# motorEncoder.net
KiCad netlist of a schematic drawn in Altium Designer
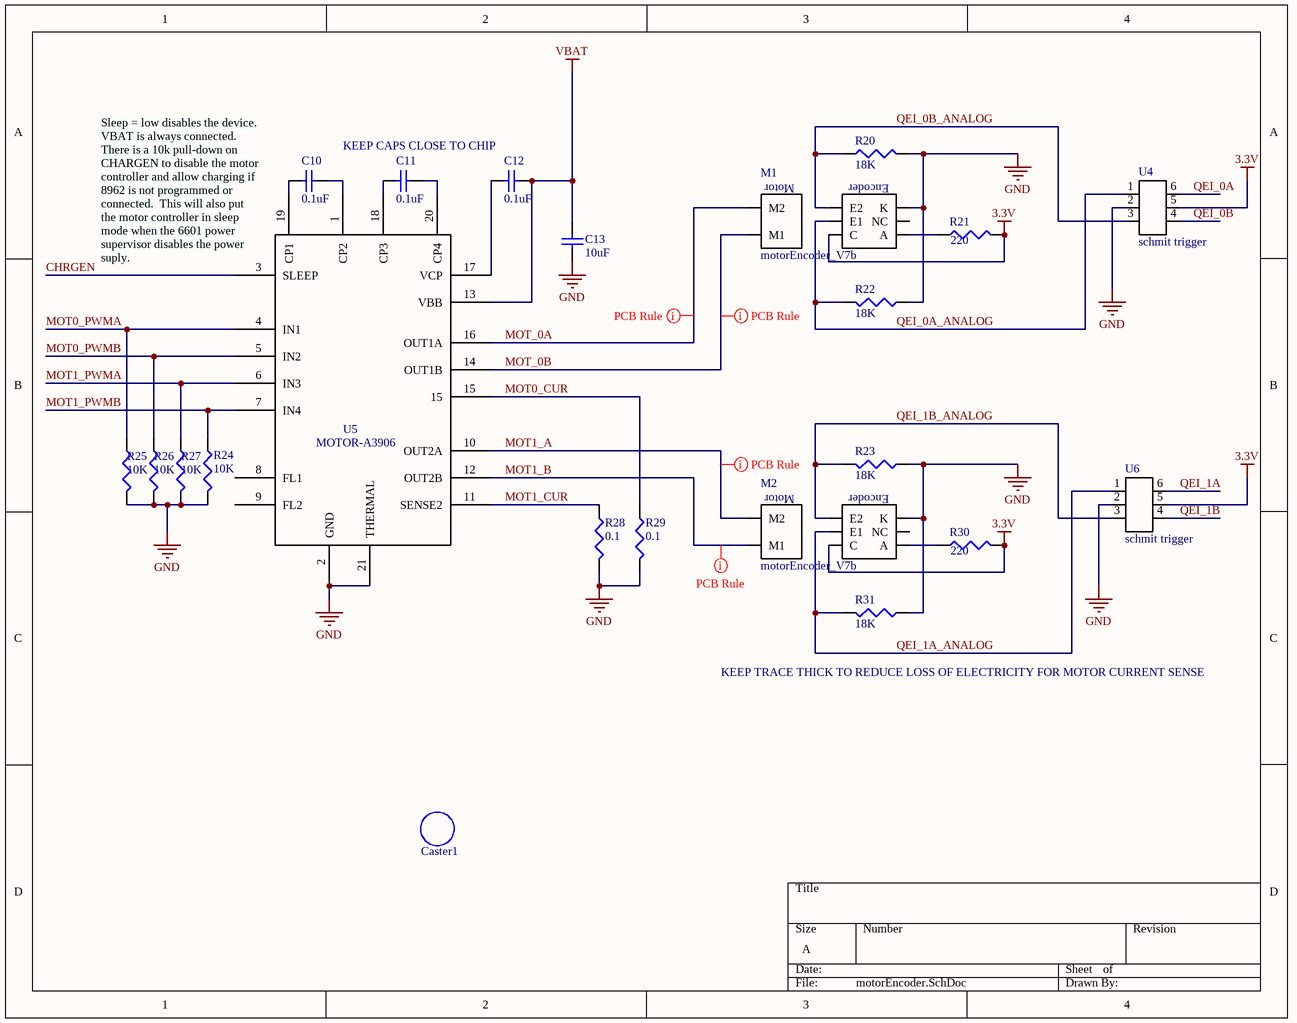
[diagram p0: motorEncoder.SchDoc]

(export (version "E")
  (design (tool "Eeschema 10.0.6"))
  (components
    (comp (ref "C10")
      (value "0.1uF")
      (footprint "CAPC1005L")
      (description "Capacitor (Semiconductor SIM Model)")
      (fields (field (name "Comment") "Cap Semi") (field (name "PUBLISHER") "Altium Limited"))
      (libsource (lib "Miscellaneous Devices") (part "Cap Semi"))
    )
    (comp (ref "C11")
      (value "0.1uF")
      (footprint "CAPC1005L")
      (description "Capacitor (Semiconductor SIM Model)")
      (fields (field (name "Comment") "Cap Semi") (field (name "PUBLISHER") "Altium Limited"))
      (libsource (lib "Miscellaneous Devices") (part "Cap Semi"))
    )
    (comp (ref "C12")
      (value "0.1uF")
      (footprint "CAPC1005L")
      (description "Capacitor (Semiconductor SIM Model)")
      (fields (field (name "Comment") "Cap Semi") (field (name "PUBLISHER") "Altium Limited"))
      (libsource (lib "Miscellaneous Devices") (part "Cap Semi"))
    )
    (comp (ref "C13")
      (value "10uF")
      (footprint "CAPC1608L")
      (description "Capacitor (Semiconductor SIM Model)")
      (fields (field (name "Comment") "Cap Semi") (field (name "PUBLISHER") "Altium Limited"))
      (libsource (lib "Miscellaneous Devices") (part "Cap Semi"))
    )
    (comp (ref "Caster1")
      (value "non connect")
      (footprint "3/4\"CASTER2")
      (description "This is just a space saver to get the caster onto the pcb")
      (libsource (lib "mrone") (part "Caster 3/4in"))
    )
    (comp (ref "M1")
      (value "motorEncoder_V7b")
      (footprint "motorEncoder_V7b")
      (libsource (lib "mrone") (part "motorEncoder_V7b"))
    )
    (comp (ref "M2")
      (value "motorEncoder_V7b")
      (footprint "motorEncoder_V7b")
      (libsource (lib "mrone") (part "motorEncoder_V7b"))
    )
    (comp (ref "R20")
      (value "18K")
      (footprint "RESC1608L")
      (description "Resistor")
      (fields (field (name "PUBLISHER") "Altium Limited"))
      (libsource (lib "Miscellaneous Devices") (part "Res3"))
    )
    (comp (ref "R21")
      (value "220")
      (footprint "RESC1608L")
      (description "Resistor")
      (fields (field (name "PUBLISHER") "Altium Limited"))
      (libsource (lib "Miscellaneous Devices") (part "Res3"))
    )
    (comp (ref "R22")
      (value "18K")
      (footprint "RESC1608L")
      (description "Resistor")
      (fields (field (name "PUBLISHER") "Altium Limited"))
      (libsource (lib "Miscellaneous Devices") (part "Res3"))
    )
    (comp (ref "R23")
      (value "18K")
      (footprint "RESC1608L")
      (description "Resistor")
      (fields (field (name "PUBLISHER") "Altium Limited"))
      (libsource (lib "Miscellaneous Devices") (part "Res3"))
    )
    (comp (ref "R24")
      (value "10K")
      (footprint "RESC1608L")
      (description "Resistor")
      (fields (field (name "Comment") "Res3") (field (name "PUBLISHER") "Altium Limited"))
      (libsource (lib "Miscellaneous Devices") (part "Res3"))
    )
    (comp (ref "R25")
      (value "10K")
      (footprint "RESC1608L")
      (description "Resistor")
      (fields (field (name "Comment") "Res3") (field (name "PUBLISHER") "Altium Limited"))
      (libsource (lib "Miscellaneous Devices") (part "Res3"))
    )
    (comp (ref "R26")
      (value "10K")
      (footprint "RESC1608L")
      (description "Resistor")
      (fields (field (name "Comment") "Res3") (field (name "PUBLISHER") "Altium Limited"))
      (libsource (lib "Miscellaneous Devices") (part "Res3"))
    )
    (comp (ref "R27")
      (value "10K")
      (footprint "RESC1608L")
      (description "Resistor")
      (fields (field (name "Comment") "Res3") (field (name "PUBLISHER") "Altium Limited"))
      (libsource (lib "Miscellaneous Devices") (part "Res3"))
    )
    (comp (ref "R28")
      (value "0.1")
      (footprint "RESC1608L")
      (description "Resistor")
      (fields (field (name "Comment") "Res3") (field (name "PUBLISHER") "Altium Limited"))
      (libsource (lib "Miscellaneous Devices") (part "Res3"))
    )
    (comp (ref "R29")
      (value "0.1")
      (footprint "RESC1608L")
      (description "Resistor")
      (fields (field (name "Comment") "Res3") (field (name "PUBLISHER") "Altium Limited"))
      (libsource (lib "Miscellaneous Devices") (part "Res3"))
    )
    (comp (ref "R30")
      (value "220")
      (footprint "RESC1608L")
      (description "Resistor")
      (fields (field (name "PUBLISHER") "Altium Limited"))
      (libsource (lib "Miscellaneous Devices") (part "Res3"))
    )
    (comp (ref "R31")
      (value "18K")
      (footprint "RESC1608L")
      (description "Resistor")
      (fields (field (name "PUBLISHER") "Altium Limited"))
      (libsource (lib "Miscellaneous Devices") (part "Res3"))
    )
    (comp (ref "U4")
      (value "schmit trigger")
      (footprint "DCK(R-PDSO-C6)")
      (libsource (lib "mrone") (part "schmit trigger"))
    )
    (comp (ref "U5")
      (value "MOTOR-A3906")
      (footprint "QFN-20")
      (libsource (lib "V2_altium") (part "MOTOR-A3906"))
    )
    (comp (ref "U6")
      (value "schmit trigger")
      (footprint "DCK(R-PDSO-C6)")
      (libsource (lib "mrone") (part "schmit trigger"))
    )
  )
  (nets
    (net (code "2") (name "/CHRGEN") (class "Default")
      (node (ref "U5") (pin "3") (pinfunction "SLEEP_3") (pintype "passive"))
    )
    (net (code "3") (name "/MOT0_CUR") (class "Default")
      (node (ref "R29") (pin "1") (pinfunction "1_1") (pintype "passive"))
      (node (ref "U5") (pin "15") (pinfunction "15_15") (pintype "passive"))
    )
    (net (code "4") (name "/MOT0_PWMA") (class "Default")
      (node (ref "R25") (pin "1") (pinfunction "1_1") (pintype "passive"))
      (node (ref "U5") (pin "4") (pinfunction "IN1_4") (pintype "passive"))
    )
    (net (code "5") (name "/MOT0_PWMB") (class "Default")
      (node (ref "R26") (pin "1") (pinfunction "1_1") (pintype "passive"))
      (node (ref "U5") (pin "5") (pinfunction "IN2_5") (pintype "passive"))
    )
    (net (code "6") (name "/MOT1_A") (class "Default")
      (node (ref "M2") (pin "M2") (pinfunction "M2_M2") (pintype "passive"))
      (node (ref "U5") (pin "10") (pinfunction "OUT2A_10") (pintype "passive"))
    )
    (net (code "7") (name "/MOT1_B") (class "Default")
      (node (ref "M2") (pin "M1") (pinfunction "M1_M1") (pintype "passive"))
      (node (ref "U5") (pin "12") (pinfunction "OUT2B_12") (pintype "passive"))
    )
    (net (code "8") (name "/MOT1_CUR") (class "Default")
      (node (ref "R28") (pin "1") (pinfunction "1_1") (pintype "passive"))
      (node (ref "U5") (pin "11") (pinfunction "SENSE2_11") (pintype "passive"))
    )
    (net (code "9") (name "/MOT1_PWMA") (class "Default")
      (node (ref "R27") (pin "1") (pinfunction "1_1") (pintype "passive"))
      (node (ref "U5") (pin "6") (pinfunction "IN3_6") (pintype "passive"))
    )
    (net (code "10") (name "/MOT1_PWMB") (class "Default")
      (node (ref "R24") (pin "1") (pinfunction "1_1") (pintype "passive"))
      (node (ref "U5") (pin "7") (pinfunction "IN4_7") (pintype "passive"))
    )
    (net (code "11") (name "/MOT_0A") (class "Default")
      (node (ref "M1") (pin "M2") (pinfunction "M2_M2") (pintype "passive"))
      (node (ref "U5") (pin "16") (pinfunction "OUT1A_16") (pintype "passive"))
    )
    (net (code "12") (name "/MOT_0B") (class "Default")
      (node (ref "M1") (pin "M1") (pinfunction "M1_M1") (pintype "passive"))
      (node (ref "U5") (pin "14") (pinfunction "OUT1B_14") (pintype "passive"))
    )
    (net (code "13") (name "/QEI_0A") (class "Default")
      (node (ref "U4") (pin "6") (pinfunction "4_6") (pintype "passive"))
    )
    (net (code "14") (name "/QEI_0A_ANALOG") (class "Default")
      (node (ref "M1") (pin "E1") (pinfunction "E1_E1") (pintype "passive"))
      (node (ref "R22") (pin "2") (pinfunction "2_2") (pintype "passive"))
      (node (ref "U4") (pin "1") (pinfunction "1_1") (pintype "passive"))
    )
    (net (code "15") (name "/QEI_0B") (class "Default")
      (node (ref "U4") (pin "4") (pinfunction "4_4") (pintype "passive"))
    )
    (net (code "16") (name "/QEI_0B_ANALOG") (class "Default")
      (node (ref "M1") (pin "E2") (pinfunction "E2_E2") (pintype "passive"))
      (node (ref "R20") (pin "1") (pinfunction "1_1") (pintype "passive"))
      (node (ref "U4") (pin "3") (pinfunction "3_3") (pintype "passive"))
    )
    (net (code "17") (name "/QEI_1A") (class "Default")
      (node (ref "U6") (pin "6") (pinfunction "4_6") (pintype "passive"))
    )
    (net (code "18") (name "/QEI_1A_ANALOG") (class "Default")
      (node (ref "M2") (pin "E1") (pinfunction "E1_E1") (pintype "passive"))
      (node (ref "R31") (pin "2") (pinfunction "2_2") (pintype "passive"))
      (node (ref "U6") (pin "1") (pinfunction "1_1") (pintype "passive"))
    )
    (net (code "19") (name "/QEI_1B") (class "Default")
      (node (ref "U6") (pin "4") (pinfunction "4_4") (pintype "passive"))
    )
    (net (code "20") (name "/QEI_1B_ANALOG") (class "Default")
      (node (ref "M2") (pin "E2") (pinfunction "E2_E2") (pintype "passive"))
      (node (ref "R23") (pin "2") (pinfunction "2_2") (pintype "passive"))
      (node (ref "U6") (pin "3") (pinfunction "3_3") (pintype "passive"))
    )
    (net (code "21") (name "3.3V") (class "Default")
      (node (ref "M1") (pin "C") (pinfunction "C_C") (pintype "passive"))
      (node (ref "M2") (pin "C") (pinfunction "C_C") (pintype "passive"))
      (node (ref "R21") (pin "2") (pinfunction "2_2") (pintype "passive"))
      (node (ref "R30") (pin "2") (pinfunction "2_2") (pintype "passive"))
      (node (ref "U4") (pin "5") (pinfunction "5_5") (pintype "passive"))
      (node (ref "U6") (pin "5") (pinfunction "5_5") (pintype "passive"))
    )
    (net (code "22") (name "GND") (class "Default")
      (node (ref "C13") (pin "1") (pinfunction "1_1") (pintype "passive"))
      (node (ref "M1") (pin "K") (pinfunction "K_K") (pintype "passive"))
      (node (ref "M2") (pin "K") (pinfunction "K_K") (pintype "passive"))
      (node (ref "R20") (pin "2") (pinfunction "2_2") (pintype "passive"))
      (node (ref "R22") (pin "1") (pinfunction "1_1") (pintype "passive"))
      (node (ref "R23") (pin "1") (pinfunction "1_1") (pintype "passive"))
      (node (ref "R24") (pin "2") (pinfunction "2_2") (pintype "passive"))
      (node (ref "R25") (pin "2") (pinfunction "2_2") (pintype "passive"))
      (node (ref "R26") (pin "2") (pinfunction "2_2") (pintype "passive"))
      (node (ref "R27") (pin "2") (pinfunction "2_2") (pintype "passive"))
      (node (ref "R28") (pin "2") (pinfunction "2_2") (pintype "passive"))
      (node (ref "R29") (pin "2") (pinfunction "2_2") (pintype "passive"))
      (node (ref "R31") (pin "1") (pinfunction "1_1") (pintype "passive"))
      (node (ref "U4") (pin "2") (pinfunction "2_2") (pintype "passive"))
      (node (ref "U5") (pin "2") (pinfunction "GND_2") (pintype "passive"))
      (node (ref "U5") (pin "21") (pinfunction "THERMAL_21") (pintype "passive"))
      (node (ref "U6") (pin "2") (pinfunction "2_2") (pintype "passive"))
    )
    (net (code "23") (name "Net-(M1-PadA)") (class "Default")
      (node (ref "M1") (pin "A") (pinfunction "A_A") (pintype "passive"))
      (node (ref "R21") (pin "1") (pinfunction "1_1") (pintype "passive"))
    )
    (net (code "24") (name "Net-(M2-PadA)") (class "Default")
      (node (ref "M2") (pin "A") (pinfunction "A_A") (pintype "passive"))
      (node (ref "R30") (pin "1") (pinfunction "1_1") (pintype "passive"))
    )
    (net (code "25") (name "Net-(U5-CP1)") (class "Default")
      (node (ref "C10") (pin "1") (pinfunction "1_1") (pintype "passive"))
      (node (ref "U5") (pin "19") (pinfunction "CP1_19") (pintype "passive"))
    )
    (net (code "26") (name "Net-(U5-CP2)") (class "Default")
      (node (ref "C10") (pin "2") (pinfunction "2_2") (pintype "passive"))
      (node (ref "U5") (pin "1") (pinfunction "CP2_1") (pintype "passive"))
    )
    (net (code "27") (name "Net-(U5-CP3)") (class "Default")
      (node (ref "C11") (pin "1") (pinfunction "1_1") (pintype "passive"))
      (node (ref "U5") (pin "18") (pinfunction "CP3_18") (pintype "passive"))
    )
    (net (code "28") (name "Net-(U5-CP4)") (class "Default")
      (node (ref "C11") (pin "2") (pinfunction "2_2") (pintype "passive"))
      (node (ref "U5") (pin "20") (pinfunction "CP4_20") (pintype "passive"))
    )
    (net (code "29") (name "Net-(U5-VCP)") (class "Default")
      (node (ref "C12") (pin "2") (pinfunction "2_2") (pintype "passive"))
      (node (ref "U5") (pin "17") (pinfunction "VCP_17") (pintype "passive"))
    )
    (net (code "30") (name "VBAT") (class "Default")
      (node (ref "C12") (pin "1") (pinfunction "1_1") (pintype "passive"))
      (node (ref "C13") (pin "2") (pinfunction "2_2") (pintype "passive"))
      (node (ref "U5") (pin "13") (pinfunction "VBB_13") (pintype "passive"))
    )
    (net (code "31") (name "unconnected-(M1-PadNC)") (class "Default")
      (node (ref "M1") (pin "NC") (pinfunction "NC_NC") (pintype "passive"))
    )
    (net (code "32") (name "unconnected-(M2-PadNC)") (class "Default")
      (node (ref "M2") (pin "NC") (pinfunction "NC_NC") (pintype "passive"))
    )
    (net (code "33") (name "unconnected-(U5-FL1-Pad8)") (class "Default")
      (node (ref "U5") (pin "8") (pinfunction "FL1_8") (pintype "passive"))
    )
    (net (code "34") (name "unconnected-(U5-FL2-Pad9)") (class "Default")
      (node (ref "U5") (pin "9") (pinfunction "FL2_9") (pintype "passive"))
    )
  )
)
